# SensorBoardTAOS.net
KiCad netlist of a schematic drawn in Altium Designer
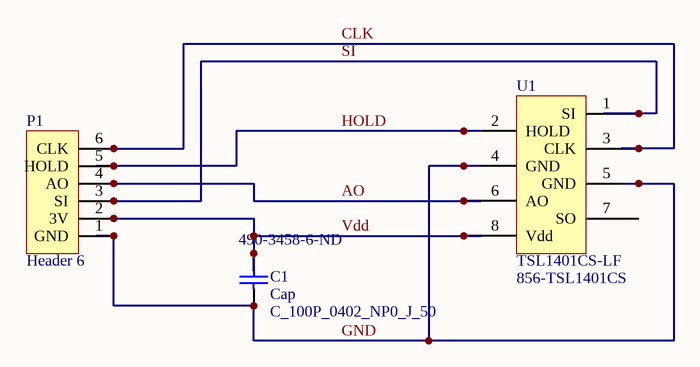
[diagram p0: SensorBoardTAOS.SchDoc]

(export (version "E")
  (design (tool "Eeschema 10.0.6"))
  (components
    (comp (ref "C1")
      (value "Cap")
      (footprint "C_0402")
      (description "Capacitor")
      (fields
        (field (name "ALTIUM_VALUE") "C_100P_0402_NP0_J_50")
        (field (name "SUPPLIER PART NUMBER 1") "490-3458-6-ND")
        (field (name "PUBLISHER") "Altium Limited")
      )
      (libsource (lib "Miscellaneous Devices") (part "Cap"))
    )
    (comp (ref "P1")
      (value "Header 6")
      (footprint "CARD EDGE 6 PIN 3X2")
      (description "Card Edge Connector, 6-Pin")
      (fields (field (name "PUBLISHER") "Altium Limited"))
      (libsource (lib "Miscellaneous Connectors") (part "Header 6"))
    )
    (comp (ref "U1")
      (value "TSL1401CS-LF")
      (footprint "TSL1401CS-LF solder bump linear array")
      (fields (field (name "SUPPLIER PART NUMBER 1") "856-TSL1401CS"))
      (libsource (lib "SensorBoard") (part "TSL1401CS-LF"))
    )
  )
  (nets
    (net (code "1") (name "/AO") (class "Default")
      (node (ref "P1") (pin "4") (pinfunction "AO_4") (pintype "passive"))
      (node (ref "U1") (pin "6") (pinfunction "AO_6") (pintype "passive"))
    )
    (net (code "2") (name "/CLK") (class "Default")
      (node (ref "P1") (pin "6") (pinfunction "CLK_6") (pintype "passive"))
      (node (ref "U1") (pin "3") (pinfunction "CLK_3") (pintype "passive"))
    )
    (net (code "3") (name "/GND") (class "Default")
      (node (ref "C1") (pin "1") (pinfunction "1_1") (pintype "passive"))
      (node (ref "P1") (pin "1") (pinfunction "GND_1") (pintype "passive"))
      (node (ref "U1") (pin "4") (pinfunction "GND_4") (pintype "passive"))
      (node (ref "U1") (pin "5") (pinfunction "GND_5") (pintype "passive"))
    )
    (net (code "4") (name "/HOLD") (class "Default")
      (node (ref "P1") (pin "5") (pinfunction "HOLD_5") (pintype "passive"))
      (node (ref "U1") (pin "2") (pinfunction "HOLD_2") (pintype "passive"))
    )
    (net (code "5") (name "/SI") (class "Default")
      (node (ref "P1") (pin "3") (pinfunction "SI_3") (pintype "passive"))
      (node (ref "U1") (pin "1") (pinfunction "SI_1") (pintype "passive"))
    )
    (net (code "6") (name "/Vdd") (class "Default")
      (node (ref "C1") (pin "2") (pinfunction "2_2") (pintype "passive"))
      (node (ref "P1") (pin "2") (pinfunction "3V_2") (pintype "passive"))
      (node (ref "U1") (pin "8") (pinfunction "Vdd_8") (pintype "passive"))
    )
    (net (code "7") (name "unconnected-(U1-SO-Pad7)") (class "Default")
      (node (ref "U1") (pin "7") (pinfunction "SO_7") (pintype "passive"))
    )
  )
)
